# arduino_stm32_vacuum_cleaner.net
KiCad netlist of a schematic drawn in EAGLE
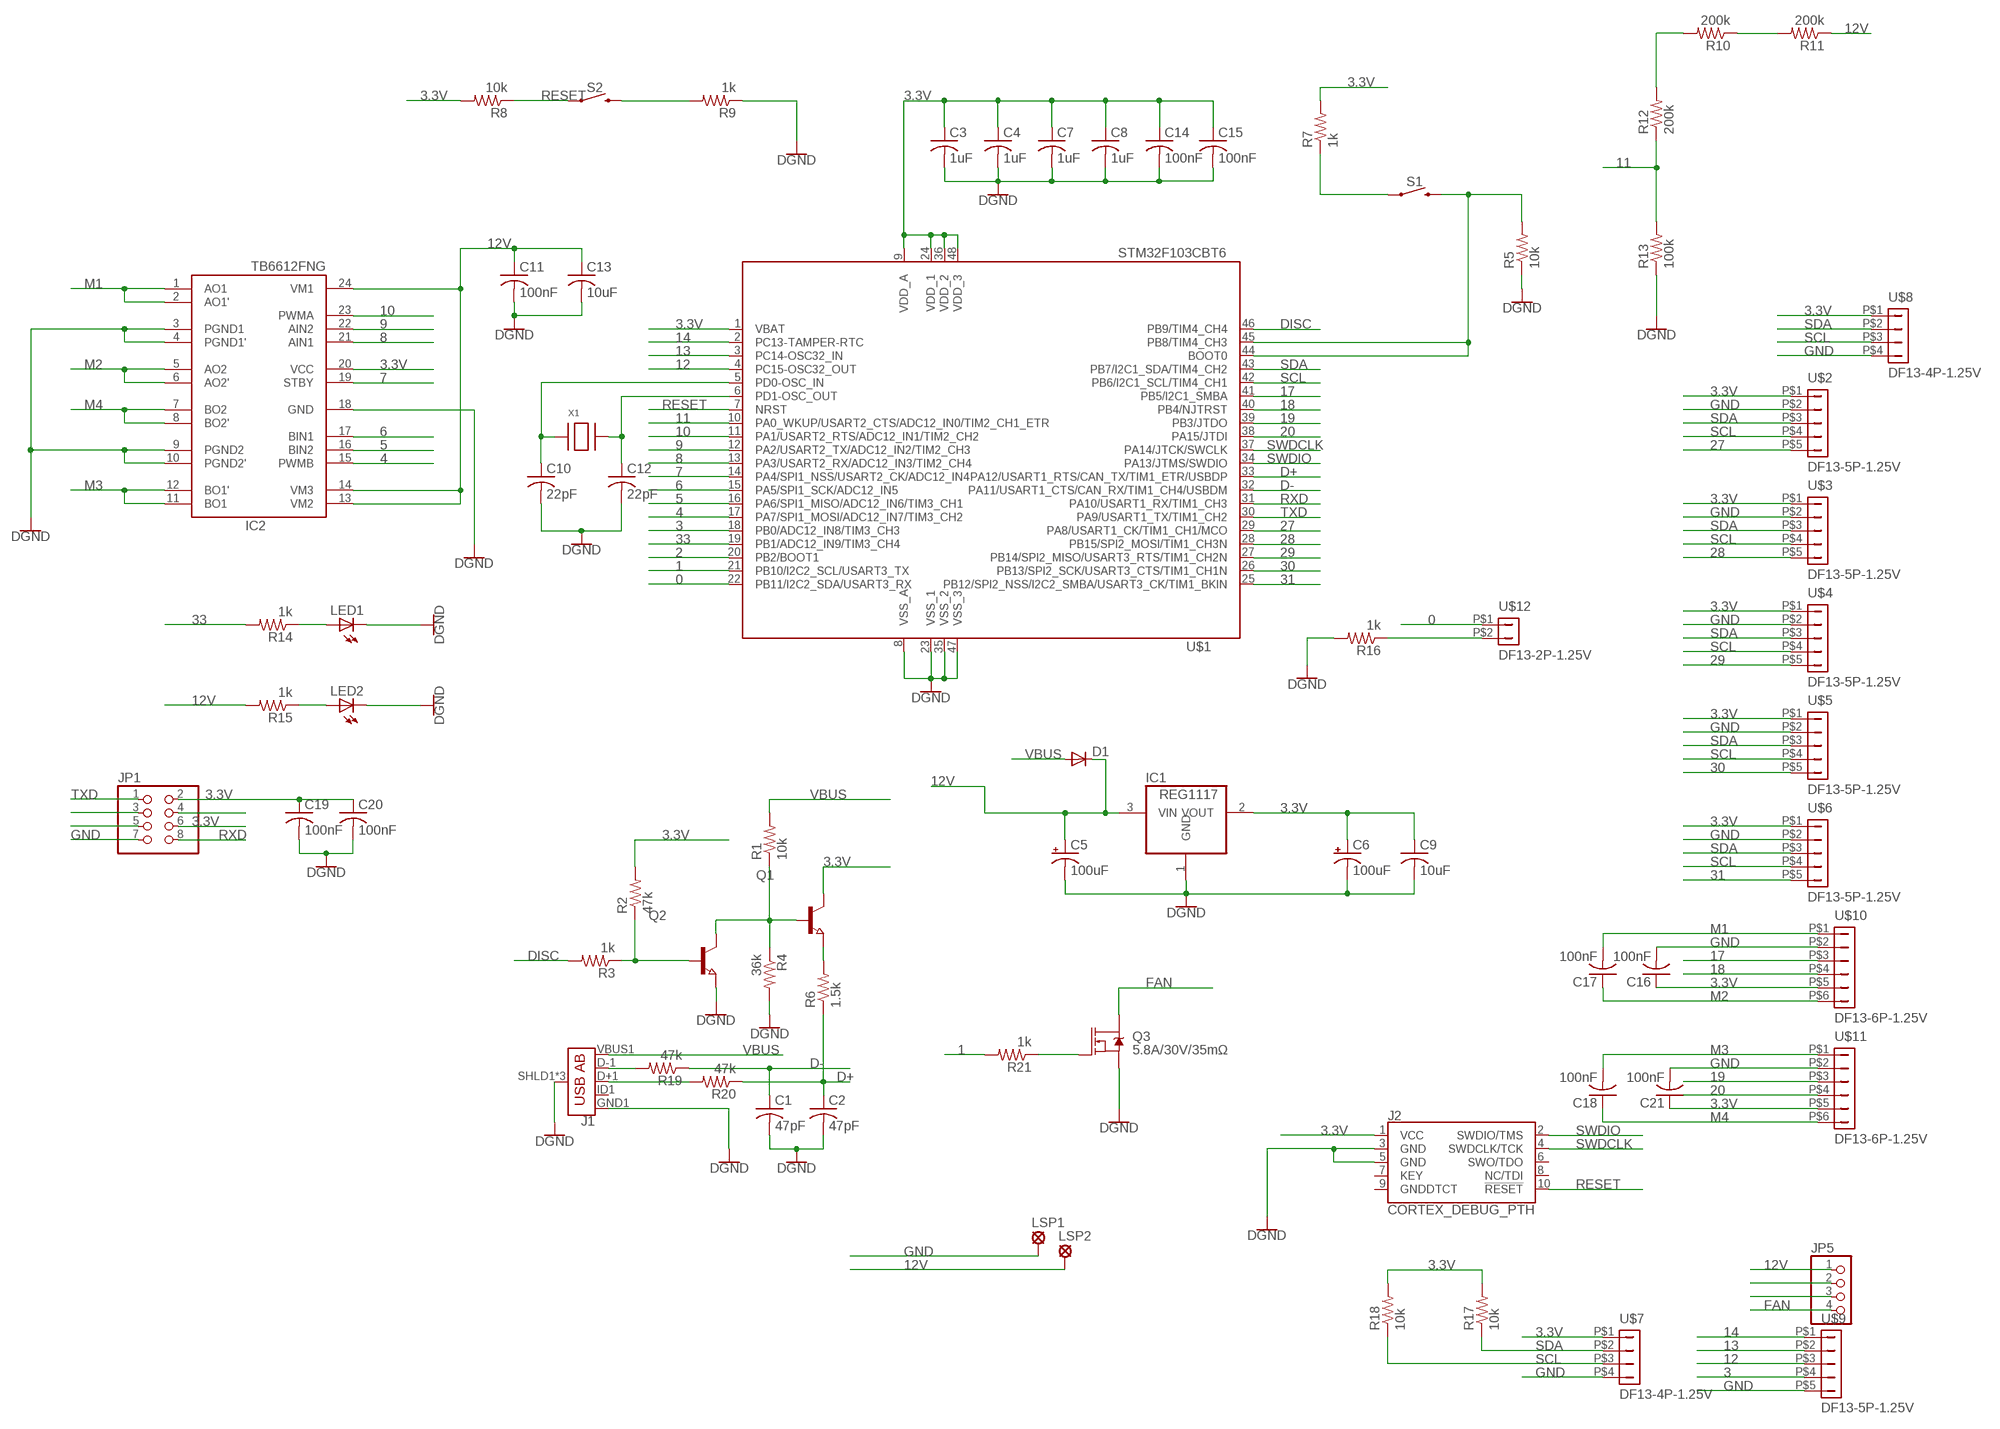
[diagram p0: schematic, sheet 1]

(export (version "E")
  (design (tool "Eeschema 10.0.6"))
  (components
    (comp (ref "C1")
      (value "47pF")
      (footprint "eagle-import:C0805")
      (libsource (lib "eagle-import") (part "C-USC0805"))
    )
    (comp (ref "C2")
      (value "47pF")
      (footprint "eagle-import:C0805")
      (libsource (lib "eagle-import") (part "C-USC0805"))
    )
    (comp (ref "C3")
      (value "1uF")
      (footprint "eagle-import:C0805")
      (libsource (lib "eagle-import") (part "C-USC0805"))
    )
    (comp (ref "C4")
      (value "1uF")
      (footprint "eagle-import:C0805")
      (libsource (lib "eagle-import") (part "C-USC0805"))
    )
    (comp (ref "C5")
      (value "100uF")
      (footprint "eagle-import:CT7343")
      (libsource (lib "eagle-import") (part "CPOL-USCT7343"))
    )
    (comp (ref "C6")
      (value "100uF")
      (footprint "eagle-import:CT7343")
      (libsource (lib "eagle-import") (part "CPOL-USCT7343"))
    )
    (comp (ref "C7")
      (value "1uF")
      (footprint "eagle-import:C0805")
      (libsource (lib "eagle-import") (part "C-USC0805"))
    )
    (comp (ref "C8")
      (value "1uF")
      (footprint "eagle-import:C0805")
      (libsource (lib "eagle-import") (part "C-USC0805"))
    )
    (comp (ref "C9")
      (value "10uF")
      (footprint "eagle-import:C0805")
      (libsource (lib "eagle-import") (part "C-USC0805"))
    )
    (comp (ref "C10")
      (value "22pF")
      (footprint "eagle-import:C0805")
      (libsource (lib "eagle-import") (part "C-USC0805"))
    )
    (comp (ref "C11")
      (value "100nF")
      (footprint "eagle-import:C0805")
      (libsource (lib "eagle-import") (part "C-USC0805"))
    )
    (comp (ref "C12")
      (value "22pF")
      (footprint "eagle-import:C0805")
      (libsource (lib "eagle-import") (part "C-USC0805"))
    )
    (comp (ref "C13")
      (value "10uF")
      (footprint "eagle-import:C0805")
      (libsource (lib "eagle-import") (part "C-USC0805"))
    )
    (comp (ref "C14")
      (value "100nF")
      (footprint "eagle-import:C0805")
      (libsource (lib "eagle-import") (part "C-USC0805"))
    )
    (comp (ref "C15")
      (value "100nF")
      (footprint "eagle-import:C0805")
      (libsource (lib "eagle-import") (part "C-USC0805"))
    )
    (comp (ref "C16")
      (value "100nF")
      (footprint "eagle-import:C0805")
      (libsource (lib "eagle-import") (part "C-USC0805"))
    )
    (comp (ref "C17")
      (value "100nF")
      (footprint "eagle-import:C0805")
      (libsource (lib "eagle-import") (part "C-USC0805"))
    )
    (comp (ref "C18")
      (value "100nF")
      (footprint "eagle-import:C0805")
      (libsource (lib "eagle-import") (part "C-USC0805"))
    )
    (comp (ref "C19")
      (value "100nF")
      (footprint "eagle-import:C0805")
      (libsource (lib "eagle-import") (part "C-USC0805"))
    )
    (comp (ref "C20")
      (value "100nF")
      (footprint "eagle-import:C0805")
      (libsource (lib "eagle-import") (part "C-USC0805"))
    )
    (comp (ref "C21")
      (value "100nF")
      (footprint "eagle-import:C0805")
      (libsource (lib "eagle-import") (part "C-USC0805"))
    )
    (comp (ref "D1")
      (value "DIODE-SOD123")
      (footprint "eagle-import:SOD123")
      (libsource (lib "eagle-import") (part "DIODE-SOD123"))
    )
    (comp (ref "IC1")
      (value "REG1117")
      (footprint "eagle-import:SOT223")
      (libsource (lib "eagle-import") (part "REG1117"))
    )
    (comp (ref "IC2")
      (value "TB6612FNG")
      (footprint "eagle-import:SSOP24")
      (libsource (lib "eagle-import") (part "TB6612FNG"))
    )
    (comp (ref "J1")
      (value "USB_AB_SMT")
      (footprint "eagle-import:USB-AB-MICRO-SMD")
      (libsource (lib "eagle-import") (part "USB_AB_SMT"))
    )
    (comp (ref "J2")
      (value "CORTEX_DEBUG_PTH")
      (footprint "eagle-import:2X5-PTH-1.27MM")
      (libsource (lib "eagle-import") (part "CORTEX_DEBUG_PTH"))
    )
    (comp (ref "JP1")
      (value "PINHD-2X4")
      (footprint "eagle-import:2X04")
      (libsource (lib "eagle-import") (part "PINHD-2X4"))
    )
    (comp (ref "JP5")
      (value "PINHD-1X4")
      (footprint "eagle-import:1X04")
      (libsource (lib "eagle-import") (part "PINHD-1X4"))
    )
    (comp (ref "LED1")
      (value "LEDCHIPLED_0603")
      (footprint "eagle-import:CHIPLED_0603")
      (libsource (lib "eagle-import") (part "LEDCHIPLED_0603"))
    )
    (comp (ref "LED2")
      (value "LEDCHIPLED_0603")
      (footprint "eagle-import:CHIPLED_0603")
      (libsource (lib "eagle-import") (part "LEDCHIPLED_0603"))
    )
    (comp (ref "LSP1")
      (value "SE14")
      (footprint "eagle-import:SE14")
      (libsource (lib "eagle-import") (part "SE14"))
    )
    (comp (ref "LSP2")
      (value "SE14")
      (footprint "eagle-import:SE14")
      (libsource (lib "eagle-import") (part "solpad_364_SE14"))
    )
    (comp (ref "Q1")
      (value "NPN-TRANSISTOR_SOT23")
      (footprint "eagle-import:SOT23")
      (libsource (lib "eagle-import") (part "NPN-TRANSISTOR_SOT23"))
    )
    (comp (ref "Q2")
      (value "NPN-TRANSISTOR_SOT23")
      (footprint "eagle-import:SOT23")
      (libsource (lib "eagle-import") (part "NPN-TRANSISTOR_SOT23"))
    )
    (comp (ref "Q3")
      (value "5.8A/30V/35mΩ")
      (footprint "eagle-import:SOT23-3")
      (libsource (lib "eagle-import") (part "MOSFET-NCH-AO3404A"))
    )
    (comp (ref "R1")
      (value "10k")
      (footprint "eagle-import:R0805")
      (libsource (lib "eagle-import") (part "R-US_R0805"))
    )
    (comp (ref "R2")
      (value "47k")
      (footprint "eagle-import:R0805")
      (libsource (lib "eagle-import") (part "R-US_R0805"))
    )
    (comp (ref "R3")
      (value "1k")
      (footprint "eagle-import:R0805")
      (libsource (lib "eagle-import") (part "R-US_R0805"))
    )
    (comp (ref "R4")
      (value "36k")
      (footprint "eagle-import:R0805")
      (libsource (lib "eagle-import") (part "R-US_R0805"))
    )
    (comp (ref "R5")
      (value "10k")
      (footprint "eagle-import:R0805")
      (libsource (lib "eagle-import") (part "R-US_R0805"))
    )
    (comp (ref "R6")
      (value "1.5k")
      (footprint "eagle-import:R0805")
      (libsource (lib "eagle-import") (part "R-US_R0805"))
    )
    (comp (ref "R7")
      (value "1k")
      (footprint "eagle-import:R0805")
      (libsource (lib "eagle-import") (part "R-US_R0805"))
    )
    (comp (ref "R8")
      (value "10k")
      (footprint "eagle-import:R0805")
      (libsource (lib "eagle-import") (part "R-US_R0805"))
    )
    (comp (ref "R9")
      (value "1k")
      (footprint "eagle-import:R0805")
      (libsource (lib "eagle-import") (part "R-US_R0805"))
    )
    (comp (ref "R10")
      (value "200k")
      (footprint "eagle-import:R1206")
      (libsource (lib "eagle-import") (part "R-US_R1206"))
    )
    (comp (ref "R11")
      (value "200k")
      (footprint "eagle-import:R1206")
      (libsource (lib "eagle-import") (part "R-US_R1206"))
    )
    (comp (ref "R12")
      (value "200k")
      (footprint "eagle-import:R1206")
      (libsource (lib "eagle-import") (part "R-US_R1206"))
    )
    (comp (ref "R13")
      (value "100k")
      (footprint "eagle-import:R1206")
      (libsource (lib "eagle-import") (part "R-US_R1206"))
    )
    (comp (ref "R14")
      (value "1k")
      (footprint "eagle-import:R0805")
      (libsource (lib "eagle-import") (part "R-US_R0805"))
    )
    (comp (ref "R15")
      (value "1k")
      (footprint "eagle-import:R0805")
      (libsource (lib "eagle-import") (part "R-US_R0805"))
    )
    (comp (ref "R16")
      (value "1k")
      (footprint "eagle-import:R0805")
      (libsource (lib "eagle-import") (part "R-US_R0805"))
    )
    (comp (ref "R17")
      (value "10k")
      (footprint "eagle-import:R0805")
      (libsource (lib "eagle-import") (part "R-US_R0805"))
    )
    (comp (ref "R18")
      (value "10k")
      (footprint "eagle-import:R0805")
      (libsource (lib "eagle-import") (part "R-US_R0805"))
    )
    (comp (ref "R19")
      (value "47k")
      (footprint "eagle-import:R0805")
      (libsource (lib "eagle-import") (part "R-US_R0805"))
    )
    (comp (ref "R20")
      (value "47k")
      (footprint "eagle-import:R0805")
      (libsource (lib "eagle-import") (part "R-US_R0805"))
    )
    (comp (ref "R21")
      (value "1k")
      (footprint "eagle-import:R0805")
      (libsource (lib "eagle-import") (part "R-US_R0805"))
    )
    (comp (ref "S1")
      (value "MOMENTARY-SWITCH-SPST-SMD-6.0X3.5MM")
      (footprint "eagle-import:TACTILE_SWITCH_SMD_6.0X3.5MM")
      (libsource (lib "eagle-import") (part "MOMENTARY-SWITCH-SPST-SMD-6.0X3.5MM"))
    )
    (comp (ref "S2")
      (value "MOMENTARY-SWITCH-SPST-SMD-6.0X3.5MM")
      (footprint "eagle-import:TACTILE_SWITCH_SMD_6.0X3.5MM")
      (libsource (lib "eagle-import") (part "MOMENTARY-SWITCH-SPST-SMD-6.0X3.5MM"))
    )
    (comp (ref "U$1")
      (value "STM32F103CBT6")
      (footprint "eagle-import:STM32_LQFP48")
      (libsource (lib "eagle-import") (part "STM32F103CBT6"))
    )
    (comp (ref "U$2")
      (value "DF13-5P-1.25V")
      (footprint "eagle-import:DF13C-5P-1.25V")
      (libsource (lib "eagle-import") (part "DF13-5P-1.25V"))
    )
    (comp (ref "U$3")
      (value "DF13-5P-1.25V")
      (footprint "eagle-import:DF13C-5P-1.25V")
      (libsource (lib "eagle-import") (part "DF13-5P-1.25V"))
    )
    (comp (ref "U$4")
      (value "DF13-5P-1.25V")
      (footprint "eagle-import:DF13C-5P-1.25V")
      (libsource (lib "eagle-import") (part "DF13-5P-1.25V"))
    )
    (comp (ref "U$5")
      (value "DF13-5P-1.25V")
      (footprint "eagle-import:DF13C-5P-1.25V")
      (libsource (lib "eagle-import") (part "DF13-5P-1.25V"))
    )
    (comp (ref "U$6")
      (value "DF13-5P-1.25V")
      (footprint "eagle-import:DF13C-5P-1.25V")
      (libsource (lib "eagle-import") (part "DF13-5P-1.25V"))
    )
    (comp (ref "U$7")
      (value "DF13-4P-1.25V")
      (footprint "eagle-import:DF13C-4P-1.25V")
      (libsource (lib "eagle-import") (part "DF13-4P-1.25V"))
    )
    (comp (ref "U$8")
      (value "DF13-4P-1.25V")
      (footprint "eagle-import:DF13C-4P-1.25V")
      (libsource (lib "eagle-import") (part "DF13-4P-1.25V"))
    )
    (comp (ref "U$9")
      (value "DF13-5P-1.25V")
      (footprint "eagle-import:DF13C-5P-1.25V")
      (libsource (lib "eagle-import") (part "DF13-5P-1.25V"))
    )
    (comp (ref "U$10")
      (value "DF13-6P-1.25V")
      (footprint "eagle-import:DF13C-6P-1.25V")
      (libsource (lib "eagle-import") (part "DF13-6P-1.25V"))
    )
    (comp (ref "U$11")
      (value "DF13-6P-1.25V")
      (footprint "eagle-import:DF13C-6P-1.25V")
      (libsource (lib "eagle-import") (part "DF13-6P-1.25V"))
    )
    (comp (ref "U$12")
      (value "DF13-2P-1.25V")
      (footprint "eagle-import:DF13C-2P-1.25V")
      (libsource (lib "eagle-import") (part "DF13-2P-1.25V"))
    )
    (comp (ref "X1")
      (value "XTALNX5032")
      (footprint "eagle-import:NX5032")
      (libsource (lib "eagle-import") (part "XTALNX5032"))
    )
  )
  (nets
    (net (code "1") (name "/0") (class "Default")
      (node (ref "U$1") (pin "22") (pinfunction "PB11/I2C2_SDA/USART3_RX_22") (pintype "input"))
      (node (ref "U$12") (pin "P$1") (pinfunction "1_P$1") (pintype "passive"))
    )
    (net (code "2") (name "/1") (class "Default")
      (node (ref "R21") (pin "2") (pinfunction "2_2") (pintype "passive"))
      (node (ref "U$1") (pin "21") (pinfunction "PB10/I2C2_SCL/USART3_TX_21") (pintype "input"))
    )
    (net (code "3") (name "/2") (class "Default")
      (node (ref "U$1") (pin "20") (pinfunction "PB2/BOOT1_20") (pintype "bidirectional"))
    )
    (net (code "4") (name "/3") (class "Default")
      (node (ref "U$1") (pin "18") (pinfunction "PB0/ADC12_IN8/TIM3_CH3_18") (pintype "bidirectional"))
      (node (ref "U$9") (pin "P$4") (pinfunction "4_P$4") (pintype "passive"))
    )
    (net (code "5") (name "/3.3V") (class "Default")
      (node (ref "C14") (pin "1") (pinfunction "1_1") (pintype "passive"))
      (node (ref "C15") (pin "1") (pinfunction "1_1") (pintype "passive"))
      (node (ref "C16") (pin "1") (pinfunction "1_1") (pintype "passive"))
      (node (ref "C19") (pin "1") (pinfunction "1_1") (pintype "passive"))
      (node (ref "C20") (pin "1") (pinfunction "1_1") (pintype "passive"))
      (node (ref "C21") (pin "1") (pinfunction "1_1") (pintype "passive"))
      (node (ref "C3") (pin "1") (pinfunction "1_1") (pintype "passive"))
      (node (ref "C4") (pin "1") (pinfunction "1_1") (pintype "passive"))
      (node (ref "C6") (pin "+") (pinfunction "+_+") (pintype "passive"))
      (node (ref "C7") (pin "1") (pinfunction "1_1") (pintype "passive"))
      (node (ref "C8") (pin "1") (pinfunction "1_1") (pintype "passive"))
      (node (ref "C9") (pin "1") (pinfunction "1_1") (pintype "passive"))
      (node (ref "IC1") (pin "2") (pinfunction "VOUT_2") (pintype "output"))
      (node (ref "IC2") (pin "20") (pinfunction "VCC_20") (pintype "power_in"))
      (node (ref "J2") (pin "1") (pinfunction "VCC_1") (pintype "bidirectional"))
      (node (ref "JP1") (pin "2") (pinfunction "2_2") (pintype "passive"))
      (node (ref "JP1") (pin "6") (pinfunction "6_6") (pintype "passive"))
      (node (ref "Q1") (pin "3") (pinfunction "C_3") (pintype "passive"))
      (node (ref "R17") (pin "2") (pinfunction "2_2") (pintype "passive"))
      (node (ref "R18") (pin "2") (pinfunction "2_2") (pintype "passive"))
      (node (ref "R2") (pin "2") (pinfunction "2_2") (pintype "passive"))
      (node (ref "R7") (pin "2") (pinfunction "2_2") (pintype "passive"))
      (node (ref "R8") (pin "2") (pinfunction "2_2") (pintype "passive"))
      (node (ref "U$1") (pin "1") (pinfunction "VBAT_1") (pintype "power_in"))
      (node (ref "U$1") (pin "24") (pinfunction "VDD_1_24") (pintype "power_in"))
      (node (ref "U$1") (pin "36") (pinfunction "VDD_2_36") (pintype "power_in"))
      (node (ref "U$1") (pin "48") (pinfunction "VDD_3_48") (pintype "power_in"))
      (node (ref "U$1") (pin "9") (pinfunction "VDD_A_9") (pintype "power_in"))
      (node (ref "U$10") (pin "P$5") (pinfunction "5_P$5") (pintype "passive"))
      (node (ref "U$11") (pin "P$5") (pinfunction "5_P$5") (pintype "passive"))
      (node (ref "U$2") (pin "P$1") (pinfunction "1_P$1") (pintype "passive"))
      (node (ref "U$3") (pin "P$1") (pinfunction "1_P$1") (pintype "passive"))
      (node (ref "U$4") (pin "P$1") (pinfunction "1_P$1") (pintype "passive"))
      (node (ref "U$5") (pin "P$1") (pinfunction "1_P$1") (pintype "passive"))
      (node (ref "U$6") (pin "P$1") (pinfunction "1_P$1") (pintype "passive"))
      (node (ref "U$7") (pin "P$1") (pinfunction "1_P$1") (pintype "passive"))
      (node (ref "U$8") (pin "P$1") (pinfunction "1_P$1") (pintype "passive"))
    )
    (net (code "6") (name "/4") (class "Default")
      (node (ref "IC2") (pin "15") (pinfunction "PWMB_15") (pintype "input"))
      (node (ref "U$1") (pin "17") (pinfunction "PA7/SPI1_MOSI/ADC12_IN7/TIM3_CH2_17") (pintype "bidirectional"))
    )
    (net (code "7") (name "/5") (class "Default")
      (node (ref "IC2") (pin "16") (pinfunction "BIN2_16") (pintype "input"))
      (node (ref "U$1") (pin "16") (pinfunction "PA6/SPI1_MISO/ADC12_IN6/TIM3_CH1_16") (pintype "bidirectional"))
    )
    (net (code "8") (name "/6") (class "Default")
      (node (ref "IC2") (pin "17") (pinfunction "BIN1_17") (pintype "input"))
      (node (ref "U$1") (pin "15") (pinfunction "PA5/SPI1_SCK/ADC12_IN5_15") (pintype "bidirectional"))
    )
    (net (code "9") (name "/7") (class "Default")
      (node (ref "IC2") (pin "19") (pinfunction "STBY_19") (pintype "input"))
      (node (ref "U$1") (pin "14") (pinfunction "PA4/SPI1_NSS/USART2_CK/ADC12_IN4_14") (pintype "bidirectional"))
    )
    (net (code "10") (name "/8") (class "Default")
      (node (ref "IC2") (pin "21") (pinfunction "AIN1_21") (pintype "input"))
      (node (ref "U$1") (pin "13") (pinfunction "PA3/USART2_RX/ADC12_IN3/TIM2_CH4_13") (pintype "bidirectional"))
    )
    (net (code "11") (name "/9") (class "Default")
      (node (ref "IC2") (pin "22") (pinfunction "AIN2_22") (pintype "input"))
      (node (ref "U$1") (pin "12") (pinfunction "PA2/USART2_TX/ADC12_IN2/TIM2_CH3_12") (pintype "bidirectional"))
    )
    (net (code "12") (name "/10") (class "Default")
      (node (ref "IC2") (pin "23") (pinfunction "PWMA_23") (pintype "input"))
      (node (ref "U$1") (pin "11") (pinfunction "PA1/USART2_RTS/ADC12_IN1/TIM2_CH2_11") (pintype "bidirectional"))
    )
    (net (code "13") (name "/11") (class "Default")
      (node (ref "R12") (pin "1") (pinfunction "1_1") (pintype "passive"))
      (node (ref "R13") (pin "2") (pinfunction "2_2") (pintype "passive"))
      (node (ref "U$1") (pin "10") (pinfunction "PA0_WKUP/USART2_CTS/ADC12_IN0/TIM2_CH1_ETR_10") (pintype "bidirectional"))
    )
    (net (code "14") (name "/12") (class "Default")
      (node (ref "U$1") (pin "4") (pinfunction "PC15-OSC32_OUT_4") (pintype "input"))
      (node (ref "U$9") (pin "P$3") (pinfunction "3_P$3") (pintype "passive"))
    )
    (net (code "15") (name "/12V") (class "Default")
      (node (ref "C11") (pin "1") (pinfunction "1_1") (pintype "passive"))
      (node (ref "C13") (pin "1") (pinfunction "1_1") (pintype "passive"))
      (node (ref "C5") (pin "+") (pinfunction "+_+") (pintype "passive"))
      (node (ref "D1") (pin "C") (pinfunction "C_C") (pintype "passive"))
      (node (ref "IC1") (pin "3") (pinfunction "VIN_3") (pintype "input"))
      (node (ref "IC2") (pin "13") (pinfunction "VM2_13") (pintype "power_in"))
      (node (ref "IC2") (pin "14") (pinfunction "VM3_14") (pintype "power_in"))
      (node (ref "IC2") (pin "24") (pinfunction "VM1_24") (pintype "power_in"))
      (node (ref "JP5") (pin "1") (pinfunction "1_1") (pintype "passive"))
      (node (ref "LSP2") (pin "MP") (pinfunction "MP_MP") (pintype "passive"))
      (node (ref "R11") (pin "1") (pinfunction "1_1") (pintype "passive"))
      (node (ref "R15") (pin "2") (pinfunction "2_2") (pintype "passive"))
    )
    (net (code "16") (name "/13") (class "Default")
      (node (ref "U$1") (pin "3") (pinfunction "PC14-OSC32_IN_3") (pintype "input"))
      (node (ref "U$9") (pin "P$2") (pinfunction "2_P$2") (pintype "passive"))
    )
    (net (code "17") (name "/14") (class "Default")
      (node (ref "U$1") (pin "2") (pinfunction "PC13-TAMPER-RTC_2") (pintype "input"))
      (node (ref "U$9") (pin "P$1") (pinfunction "1_P$1") (pintype "passive"))
    )
    (net (code "18") (name "/17") (class "Default")
      (node (ref "U$1") (pin "41") (pinfunction "PB5/I2C1_SMBA_41") (pintype "input"))
      (node (ref "U$10") (pin "P$3") (pinfunction "3_P$3") (pintype "passive"))
    )
    (net (code "19") (name "/18") (class "Default")
      (node (ref "U$1") (pin "40") (pinfunction "PB4/NJTRST_40") (pintype "bidirectional"))
      (node (ref "U$10") (pin "P$4") (pinfunction "4_P$4") (pintype "passive"))
    )
    (net (code "20") (name "/19") (class "Default")
      (node (ref "U$1") (pin "39") (pinfunction "PB3/JTDO_39") (pintype "bidirectional"))
      (node (ref "U$11") (pin "P$3") (pinfunction "3_P$3") (pintype "passive"))
    )
    (net (code "21") (name "/20") (class "Default")
      (node (ref "U$1") (pin "38") (pinfunction "PA15/JTDI_38") (pintype "bidirectional"))
      (node (ref "U$11") (pin "P$4") (pinfunction "4_P$4") (pintype "passive"))
    )
    (net (code "22") (name "/27") (class "Default")
      (node (ref "U$1") (pin "29") (pinfunction "PA8/USART1_CK/TIM1_CH1/MCO_29") (pintype "bidirectional"))
      (node (ref "U$2") (pin "P$5") (pinfunction "5_P$5") (pintype "passive"))
    )
    (net (code "23") (name "/28") (class "Default")
      (node (ref "U$1") (pin "28") (pinfunction "PB15/SPI2_MOSI/TIM1_CH3N_28") (pintype "input"))
      (node (ref "U$3") (pin "P$5") (pinfunction "5_P$5") (pintype "passive"))
    )
    (net (code "24") (name "/29") (class "Default")
      (node (ref "U$1") (pin "27") (pinfunction "PB14/SPI2_MISO/USART3_RTS/TIM1_CH2N_27") (pintype "input"))
      (node (ref "U$4") (pin "P$5") (pinfunction "5_P$5") (pintype "passive"))
    )
    (net (code "25") (name "/30") (class "Default")
      (node (ref "U$1") (pin "26") (pinfunction "PB13/SPI2_SCK/USART3_CTS/TIM1_CH1N_26") (pintype "input"))
      (node (ref "U$5") (pin "P$5") (pinfunction "5_P$5") (pintype "passive"))
    )
    (net (code "26") (name "/31") (class "Default")
      (node (ref "U$1") (pin "25") (pinfunction "PB12/SPI2_NSS/I2C2_SMBA/USART3_CK/TIM1_BKIN_25") (pintype "input"))
      (node (ref "U$6") (pin "P$5") (pinfunction "5_P$5") (pintype "passive"))
    )
    (net (code "27") (name "/33") (class "Default")
      (node (ref "R14") (pin "2") (pinfunction "2_2") (pintype "passive"))
      (node (ref "U$1") (pin "19") (pinfunction "PB1/ADC12_IN9/TIM3_CH4_19") (pintype "bidirectional"))
    )
    (net (code "28") (name "/D+") (class "Default")
      (node (ref "C2") (pin "1") (pinfunction "1_1") (pintype "passive"))
      (node (ref "R20") (pin "1") (pinfunction "1_1") (pintype "passive"))
      (node (ref "R6") (pin "1") (pinfunction "1_1") (pintype "passive"))
      (node (ref "U$1") (pin "33") (pinfunction "PA12/USART1_RTS/CAN_TX/TIM1_ETR/USBDP_33") (pintype "bidirectional"))
    )
    (net (code "29") (name "/D-") (class "Default")
      (node (ref "C1") (pin "1") (pinfunction "1_1") (pintype "passive"))
      (node (ref "R19") (pin "1") (pinfunction "1_1") (pintype "passive"))
      (node (ref "U$1") (pin "32") (pinfunction "PA11/USART1_CTS/CAN_RX/TIM1_CH4/USBDM_32") (pintype "bidirectional"))
    )
    (net (code "30") (name "/DISC") (class "Default")
      (node (ref "R3") (pin "2") (pinfunction "2_2") (pintype "passive"))
      (node (ref "U$1") (pin "46") (pinfunction "PB9/TIM4_CH4_46") (pintype "input"))
    )
    (net (code "31") (name "/FAN") (class "Default")
      (node (ref "JP5") (pin "4") (pinfunction "4_4") (pintype "passive"))
      (node (ref "Q3") (pin "3") (pinfunction "D_3") (pintype "bidirectional"))
    )
    (net (code "32") (name "/M1") (class "Default")
      (node (ref "C17") (pin "2") (pinfunction "2_2") (pintype "passive"))
      (node (ref "IC2") (pin "1") (pinfunction "AO1_1") (pintype "output"))
      (node (ref "IC2") (pin "2") (pinfunction "AO1'_2") (pintype "output"))
      (node (ref "U$10") (pin "P$1") (pinfunction "1_P$1") (pintype "passive"))
    )
    (net (code "33") (name "/M2") (class "Default")
      (node (ref "C17") (pin "1") (pinfunction "1_1") (pintype "passive"))
      (node (ref "IC2") (pin "5") (pinfunction "AO2_5") (pintype "output"))
      (node (ref "IC2") (pin "6") (pinfunction "AO2'_6") (pintype "output"))
      (node (ref "U$10") (pin "P$6") (pinfunction "6_P$6") (pintype "passive"))
    )
    (net (code "34") (name "/M3") (class "Default")
      (node (ref "C18") (pin "2") (pinfunction "2_2") (pintype "passive"))
      (node (ref "IC2") (pin "11") (pinfunction "BO1_11") (pintype "output"))
      (node (ref "IC2") (pin "12") (pinfunction "BO1'_12") (pintype "output"))
      (node (ref "U$11") (pin "P$1") (pinfunction "1_P$1") (pintype "passive"))
    )
    (net (code "35") (name "/M4") (class "Default")
      (node (ref "C18") (pin "1") (pinfunction "1_1") (pintype "passive"))
      (node (ref "IC2") (pin "7") (pinfunction "BO2_7") (pintype "output"))
      (node (ref "IC2") (pin "8") (pinfunction "BO2'_8") (pintype "output"))
      (node (ref "U$11") (pin "P$6") (pinfunction "6_P$6") (pintype "passive"))
    )
    (net (code "36") (name "/RESET") (class "Default")
      (node (ref "J2") (pin "10") (pinfunction "~{RESET}_10") (pintype "bidirectional"))
      (node (ref "R8") (pin "1") (pinfunction "1_1") (pintype "passive"))
      (node (ref "S2") (pin "1") (pinfunction "1_1") (pintype "passive"))
      (node (ref "U$1") (pin "7") (pinfunction "NRST_7") (pintype "input"))
    )
    (net (code "37") (name "/RXD") (class "Default")
      (node (ref "JP1") (pin "8") (pinfunction "8_8") (pintype "passive"))
      (node (ref "U$1") (pin "31") (pinfunction "PA10/USART1_RX/TIM1_CH3_31") (pintype "bidirectional"))
    )
    (net (code "38") (name "/SCL") (class "Default")
      (node (ref "R18") (pin "1") (pinfunction "1_1") (pintype "passive"))
      (node (ref "U$1") (pin "42") (pinfunction "PB6/I2C1_SCL/TIM4_CH1_42") (pintype "input"))
      (node (ref "U$2") (pin "P$4") (pinfunction "4_P$4") (pintype "passive"))
      (node (ref "U$3") (pin "P$4") (pinfunction "4_P$4") (pintype "passive"))
      (node (ref "U$4") (pin "P$4") (pinfunction "4_P$4") (pintype "passive"))
      (node (ref "U$5") (pin "P$4") (pinfunction "4_P$4") (pintype "passive"))
      (node (ref "U$6") (pin "P$4") (pinfunction "4_P$4") (pintype "passive"))
      (node (ref "U$7") (pin "P$3") (pinfunction "3_P$3") (pintype "passive"))
      (node (ref "U$8") (pin "P$3") (pinfunction "3_P$3") (pintype "passive"))
    )
    (net (code "39") (name "/SDA") (class "Default")
      (node (ref "R17") (pin "1") (pinfunction "1_1") (pintype "passive"))
      (node (ref "U$1") (pin "43") (pinfunction "PB7/I2C1_SDA/TIM4_CH2_43") (pintype "bidirectional"))
      (node (ref "U$2") (pin "P$3") (pinfunction "3_P$3") (pintype "passive"))
      (node (ref "U$3") (pin "P$3") (pinfunction "3_P$3") (pintype "passive"))
      (node (ref "U$4") (pin "P$3") (pinfunction "3_P$3") (pintype "passive"))
      (node (ref "U$5") (pin "P$3") (pinfunction "3_P$3") (pintype "passive"))
      (node (ref "U$6") (pin "P$3") (pinfunction "3_P$3") (pintype "passive"))
      (node (ref "U$7") (pin "P$2") (pinfunction "2_P$2") (pintype "passive"))
      (node (ref "U$8") (pin "P$2") (pinfunction "2_P$2") (pintype "passive"))
    )
    (net (code "40") (name "/SWDCLK") (class "Default")
      (node (ref "J2") (pin "4") (pinfunction "SWDCLK/TCK_4") (pintype "bidirectional"))
      (node (ref "U$1") (pin "37") (pinfunction "PA14/JTCK/SWCLK_37") (pintype "bidirectional"))
    )
    (net (code "41") (name "/SWDIO") (class "Default")
      (node (ref "J2") (pin "2") (pinfunction "SWDIO/TMS_2") (pintype "bidirectional"))
      (node (ref "U$1") (pin "34") (pinfunction "PA13/JTMS/SWDIO_34") (pintype "bidirectional"))
    )
    (net (code "42") (name "/TXD") (class "Default")
      (node (ref "JP1") (pin "1") (pinfunction "1_1") (pintype "passive"))
      (node (ref "U$1") (pin "30") (pinfunction "PA9/USART1_TX/TIM1_CH2_30") (pintype "input"))
    )
    (net (code "43") (name "/VBUS") (class "Default")
      (node (ref "D1") (pin "A") (pinfunction "A_A") (pintype "passive"))
      (node (ref "J1") (pin "VBUS1") (pinfunction "VBUS_VBUS1") (pintype "power_in"))
      (node (ref "R1") (pin "2") (pinfunction "2_2") (pintype "passive"))
    )
    (net (code "44") (name "DGND") (class "Default")
      (node (ref "C1") (pin "2") (pinfunction "2_2") (pintype "passive"))
      (node (ref "C10") (pin "2") (pinfunction "2_2") (pintype "passive"))
      (node (ref "C11") (pin "2") (pinfunction "2_2") (pintype "passive"))
      (node (ref "C12") (pin "2") (pinfunction "2_2") (pintype "passive"))
      (node (ref "C13") (pin "2") (pinfunction "2_2") (pintype "passive"))
      (node (ref "C14") (pin "2") (pinfunction "2_2") (pintype "passive"))
      (node (ref "C15") (pin "2") (pinfunction "2_2") (pintype "passive"))
      (node (ref "C16") (pin "2") (pinfunction "2_2") (pintype "passive"))
      (node (ref "C19") (pin "2") (pinfunction "2_2") (pintype "passive"))
      (node (ref "C2") (pin "2") (pinfunction "2_2") (pintype "passive"))
      (node (ref "C20") (pin "2") (pinfunction "2_2") (pintype "passive"))
      (node (ref "C21") (pin "2") (pinfunction "2_2") (pintype "passive"))
      (node (ref "C3") (pin "2") (pinfunction "2_2") (pintype "passive"))
      (node (ref "C4") (pin "2") (pinfunction "2_2") (pintype "passive"))
      (node (ref "C5") (pin "-") (pinfunction "-_-") (pintype "passive"))
      (node (ref "C6") (pin "-") (pinfunction "-_-") (pintype "passive"))
      (node (ref "C7") (pin "2") (pinfunction "2_2") (pintype "passive"))
      (node (ref "C8") (pin "2") (pinfunction "2_2") (pintype "passive"))
      (node (ref "C9") (pin "2") (pinfunction "2_2") (pintype "passive"))
      (node (ref "IC1") (pin "1") (pinfunction "GND_1") (pintype "power_in"))
      (node (ref "IC2") (pin "10") (pinfunction "PGND2'_10") (pintype "power_in"))
      (node (ref "IC2") (pin "18") (pinfunction "GND_18") (pintype "power_in"))
      (node (ref "IC2") (pin "3") (pinfunction "PGND1_3") (pintype "power_in"))
      (node (ref "IC2") (pin "4") (pinfunction "PGND1'_4") (pintype "power_in"))
      (node (ref "IC2") (pin "9") (pinfunction "PGND2_9") (pintype "power_in"))
      (node (ref "J1") (pin "GND1") (pinfunction "GND_GND1") (pintype "power_in"))
      (node (ref "J1") (pin "SHLD1") (pinfunction "SHIELD_SHLD1") (pintype "bidirectional"))
      (node (ref "J1") (pin "SHLD2") (pinfunction "SHIELD_SHLD2") (pintype "bidirectional"))
      (node (ref "J1") (pin "SHLD3") (pinfunction "SHIELD_SHLD3") (pintype "bidirectional"))
      (node (ref "J2") (pin "3") (pinfunction "GND_3") (pintype "bidirectional"))
      (node (ref "J2") (pin "5") (pinfunction "GND_5") (pintype "bidirectional"))
      (node (ref "JP1") (pin "7") (pinfunction "7_7") (pintype "passive"))
      (node (ref "LED1") (pin "C") (pinfunction "C_C") (pintype "passive"))
      (node (ref "LED2") (pin "C") (pinfunction "C_C") (pintype "passive"))
      (node (ref "LSP1") (pin "MP") (pinfunction "MP_MP") (pintype "passive"))
      (node (ref "Q2") (pin "2") (pinfunction "E_2") (pintype "passive"))
      (node (ref "Q3") (pin "2") (pinfunction "S_2") (pintype "bidirectional"))
      (node (ref "R13") (pin "1") (pinfunction "1_1") (pintype "passive"))
      (node (ref "R16") (pin "2") (pinfunction "2_2") (pintype "passive"))
      (node (ref "R4") (pin "2") (pinfunction "2_2") (pintype "passive"))
      (node (ref "R5") (pin "1") (pinfunction "1_1") (pintype "passive"))
      (node (ref "R9") (pin "1") (pinfunction "1_1") (pintype "passive"))
      (node (ref "U$1") (pin "23") (pinfunction "VSS_1_23") (pintype "power_in"))
      (node (ref "U$1") (pin "35") (pinfunction "VSS_2_35") (pintype "power_in"))
      (node (ref "U$1") (pin "47") (pinfunction "VSS_3_47") (pintype "power_in"))
      (node (ref "U$1") (pin "8") (pinfunction "VSS_A_8") (pintype "power_in"))
      (node (ref "U$10") (pin "P$2") (pinfunction "2_P$2") (pintype "passive"))
      (node (ref "U$11") (pin "P$2") (pinfunction "2_P$2") (pintype "passive"))
      (node (ref "U$2") (pin "P$2") (pinfunction "2_P$2") (pintype "passive"))
      (node (ref "U$3") (pin "P$2") (pinfunction "2_P$2") (pintype "passive"))
      (node (ref "U$4") (pin "P$2") (pinfunction "2_P$2") (pintype "passive"))
      (node (ref "U$5") (pin "P$2") (pinfunction "2_P$2") (pintype "passive"))
      (node (ref "U$6") (pin "P$2") (pinfunction "2_P$2") (pintype "passive"))
      (node (ref "U$7") (pin "P$4") (pinfunction "4_P$4") (pintype "passive"))
      (node (ref "U$8") (pin "P$4") (pinfunction "4_P$4") (pintype "passive"))
      (node (ref "U$9") (pin "P$5") (pinfunction "5_P$5") (pintype "passive"))
    )
    (net (code "45") (name "Net-(J1-D+)") (class "Default")
      (node (ref "J1") (pin "D+1") (pinfunction "D+_D+1") (pintype "bidirectional"))
      (node (ref "R20") (pin "2") (pinfunction "2_2") (pintype "passive"))
    )
    (net (code "46") (name "Net-(J1-D-)") (class "Default")
      (node (ref "J1") (pin "D-1") (pinfunction "D-_D-1") (pintype "bidirectional"))
      (node (ref "R19") (pin "2") (pinfunction "2_2") (pintype "passive"))
    )
    (net (code "47") (name "Net-(LED1-PadA)") (class "Default")
      (node (ref "LED1") (pin "A") (pinfunction "A_A") (pintype "passive"))
      (node (ref "R14") (pin "1") (pinfunction "1_1") (pintype "passive"))
    )
    (net (code "48") (name "Net-(LED2-PadA)") (class "Default")
      (node (ref "LED2") (pin "A") (pinfunction "A_A") (pintype "passive"))
      (node (ref "R15") (pin "1") (pinfunction "1_1") (pintype "passive"))
    )
    (net (code "49") (name "Net-(Q1-B)") (class "Default")
      (node (ref "Q1") (pin "1") (pinfunction "B_1") (pintype "passive"))
      (node (ref "Q2") (pin "3") (pinfunction "C_3") (pintype "passive"))
      (node (ref "R1") (pin "1") (pinfunction "1_1") (pintype "passive"))
      (node (ref "R4") (pin "1") (pinfunction "1_1") (pintype "passive"))
    )
    (net (code "50") (name "Net-(Q1-E)") (class "Default")
      (node (ref "Q1") (pin "2") (pinfunction "E_2") (pintype "passive"))
      (node (ref "R6") (pin "2") (pinfunction "2_2") (pintype "passive"))
    )
    (net (code "51") (name "Net-(Q2-B)") (class "Default")
      (node (ref "Q2") (pin "1") (pinfunction "B_1") (pintype "passive"))
      (node (ref "R2") (pin "1") (pinfunction "1_1") (pintype "passive"))
      (node (ref "R3") (pin "1") (pinfunction "1_1") (pintype "passive"))
    )
    (net (code "52") (name "Net-(Q3-G)") (class "Default")
      (node (ref "Q3") (pin "1") (pinfunction "G_1") (pintype "bidirectional"))
      (node (ref "R21") (pin "1") (pinfunction "1_1") (pintype "passive"))
    )
    (net (code "53") (name "Net-(R7-Pad1)") (class "Default")
      (node (ref "R7") (pin "1") (pinfunction "1_1") (pintype "passive"))
      (node (ref "S1") (pin "1") (pinfunction "1_1") (pintype "passive"))
    )
    (net (code "54") (name "Net-(R9-Pad2)") (class "Default")
      (node (ref "R9") (pin "2") (pinfunction "2_2") (pintype "passive"))
      (node (ref "S2") (pin "2") (pinfunction "2_2") (pintype "passive"))
    )
    (net (code "55") (name "Net-(R10-Pad1)") (class "Default")
      (node (ref "R10") (pin "1") (pinfunction "1_1") (pintype "passive"))
      (node (ref "R11") (pin "2") (pinfunction "2_2") (pintype "passive"))
    )
    (net (code "56") (name "Net-(R10-Pad2)") (class "Default")
      (node (ref "R10") (pin "2") (pinfunction "2_2") (pintype "passive"))
      (node (ref "R12") (pin "2") (pinfunction "2_2") (pintype "passive"))
    )
    (net (code "57") (name "Net-(U$1-BOOT0)") (class "Default")
      (node (ref "R5") (pin "2") (pinfunction "2_2") (pintype "passive"))
      (node (ref "S1") (pin "2") (pinfunction "2_2") (pintype "passive"))
      (node (ref "U$1") (pin "44") (pinfunction "BOOT0_44") (pintype "input"))
      (node (ref "U$1") (pin "45") (pinfunction "PB8/TIM4_CH3_45") (pintype "bidirectional"))
    )
    (net (code "58") (name "Net-(U$1-PD0-OSC_IN)") (class "Default")
      (node (ref "C10") (pin "1") (pinfunction "1_1") (pintype "passive"))
      (node (ref "U$1") (pin "5") (pinfunction "PD0-OSC_IN_5") (pintype "input"))
      (node (ref "X1") (pin "P$1") (pinfunction "P$1_P$1") (pintype "bidirectional"))
    )
    (net (code "59") (name "Net-(U$1-PD1-OSC_OUT)") (class "Default")
      (node (ref "C12") (pin "1") (pinfunction "1_1") (pintype "passive"))
      (node (ref "U$1") (pin "6") (pinfunction "PD1-OSC_OUT_6") (pintype "input"))
      (node (ref "X1") (pin "P$2") (pinfunction "P$2_P$2") (pintype "bidirectional"))
    )
    (net (code "60") (name "Net-(U$12-2)") (class "Default")
      (node (ref "R16") (pin "1") (pinfunction "1_1") (pintype "passive"))
      (node (ref "U$12") (pin "P$2") (pinfunction "2_P$2") (pintype "passive"))
    )
    (net (code "61") (name "unconnected-(J1-USBID-PadID1)") (class "Default")
      (node (ref "J1") (pin "ID1") (pinfunction "USBID_ID1") (pintype "bidirectional"))
    )
    (net (code "62") (name "unconnected-(J2-GNDDTCT-Pad9)") (class "Default")
      (node (ref "J2") (pin "9") (pinfunction "GNDDTCT_9") (pintype "bidirectional"))
    )
    (net (code "63") (name "unconnected-(J2-KEY-Pad7)") (class "Default")
      (node (ref "J2") (pin "7") (pinfunction "KEY_7") (pintype "bidirectional"))
    )
    (net (code "64") (name "unconnected-(J2-NC{slash}TDI-Pad8)") (class "Default")
      (node (ref "J2") (pin "8") (pinfunction "NC/TDI_8") (pintype "bidirectional"))
    )
    (net (code "65") (name "unconnected-(J2-SWO{slash}TDO-Pad6)") (class "Default")
      (node (ref "J2") (pin "6") (pinfunction "SWO/TDO_6") (pintype "bidirectional"))
    )
    (net (code "66") (name "unconnected-(JP1-Pad3)") (class "Default")
      (node (ref "JP1") (pin "3") (pinfunction "3_3") (pintype "passive"))
    )
    (net (code "67") (name "unconnected-(JP1-Pad4)") (class "Default")
      (node (ref "JP1") (pin "4") (pinfunction "4_4") (pintype "passive"))
    )
    (net (code "68") (name "unconnected-(JP1-Pad5)") (class "Default")
      (node (ref "JP1") (pin "5") (pinfunction "5_5") (pintype "passive"))
    )
    (net (code "69") (name "unconnected-(JP5-Pad2)") (class "Default")
      (node (ref "JP5") (pin "2") (pinfunction "2_2") (pintype "passive"))
    )
    (net (code "70") (name "unconnected-(JP5-Pad3)") (class "Default")
      (node (ref "JP5") (pin "3") (pinfunction "3_3") (pintype "passive"))
    )
  )
)
